# Sheet1.net
KiCad netlist of a schematic drawn in Altium Designer
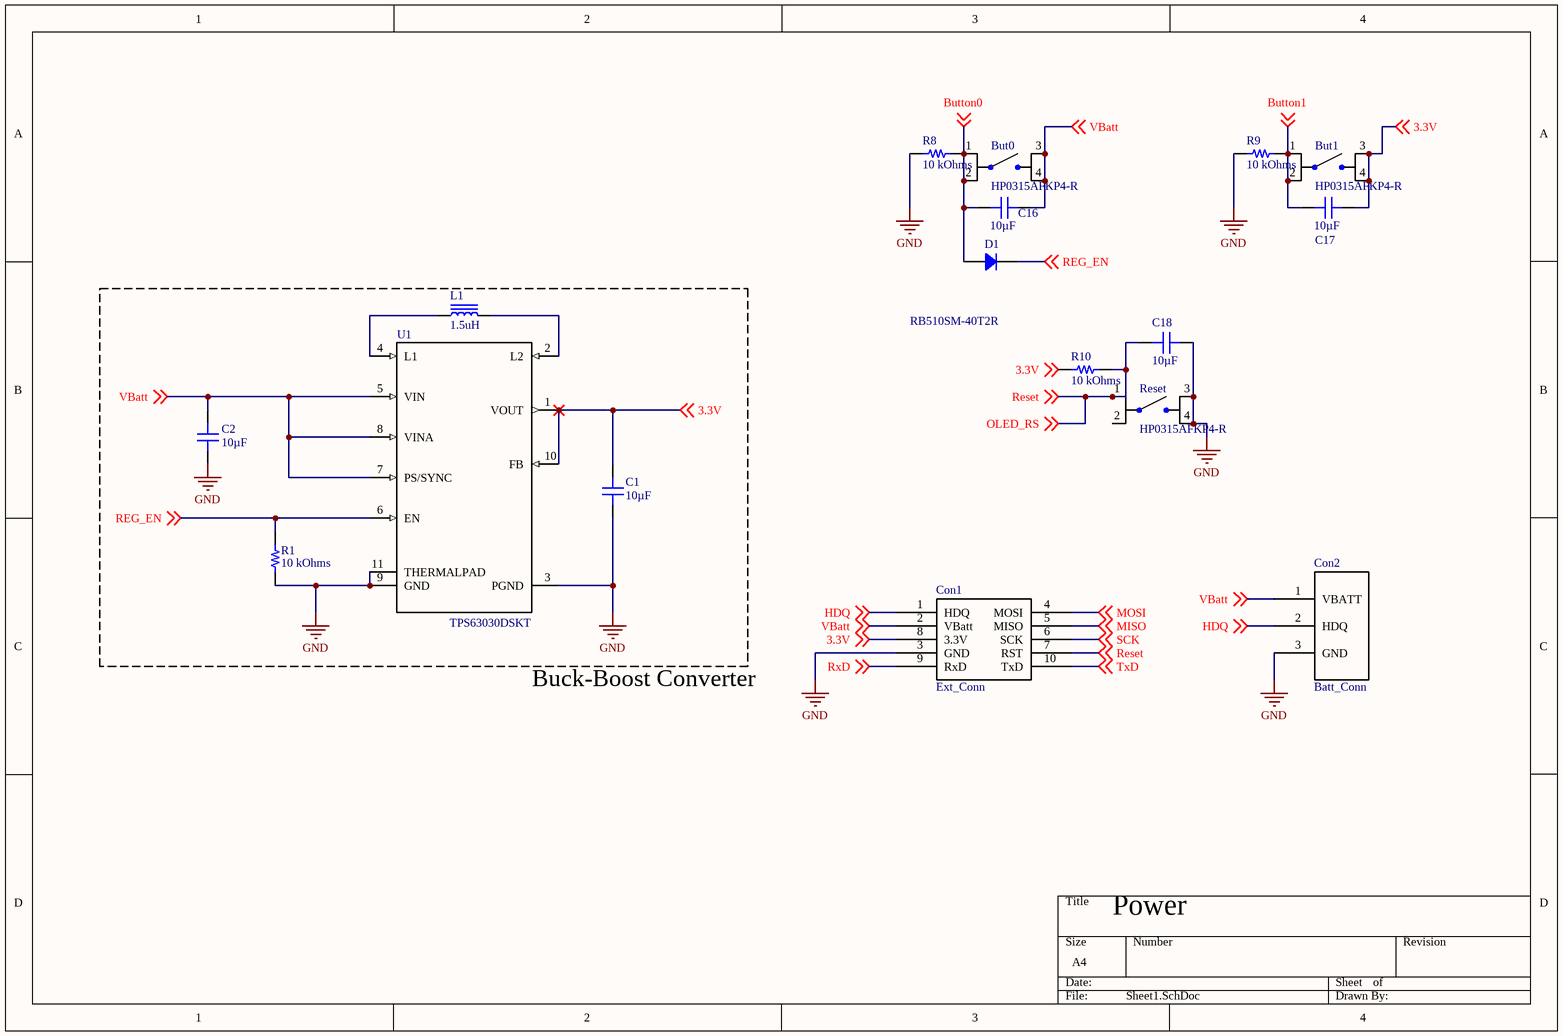
[diagram p0: Sheet1.SchDoc]

(export (version "E")
  (design (tool "Eeschema 10.0.6"))
  (components
    (comp (ref "But0")
      (value "HP0315AFKP4-R")
      (footprint "*SW_HP0315AFKP4-R")
      (description "Tactile Switch SPST-NO Top Actuated Surface Mount")
      (fields (field (name "MF") "NKK Switches"))
      (libsource (lib "ugurkrcl Lib") (part "HP0315AFKP4-R"))
    )
    (comp (ref "But1")
      (value "HP0315AFKP4-R")
      (footprint "*SW_HP0315AFKP4-R")
      (description "Tactile Switch SPST-NO Top Actuated Surface Mount")
      (fields (field (name "MF") "NKK Switches"))
      (libsource (lib "ugurkrcl Lib") (part "HP0315AFKP4-R"))
    )
    (comp (ref "C1")
      (value "10µF")
      (footprint "CAP 0402_1005")
      (description "CAP CER 10UF 10V X5R 0402")
      (fields
        (field (name "PART NUMBER") "CL05A106MP8NUB8")
        (field (name "MANUFACTURER") "Samsung Electro-Mechanics")
      )
      (libsource (lib "Celestial Altium Library - altium_library") (part "Capacitor"))
    )
    (comp (ref "C2")
      (value "10µF")
      (footprint "CAP 0402_1005")
      (description "CAP CER 10UF 10V X5R 0402")
      (fields
        (field (name "PART NUMBER") "CL05A106MP8NUB8")
        (field (name "MANUFACTURER") "Samsung Electro-Mechanics")
      )
      (libsource (lib "Celestial Altium Library - altium_library") (part "Capacitor"))
    )
    (comp (ref "C16")
      (value "10µF")
      (footprint "CAP 0402_1005")
      (description "CAP CER 10UF 10V X5R 0402")
      (fields
        (field (name "PART NUMBER") "CL05A106MP8NUB8")
        (field (name "MANUFACTURER") "Samsung Electro-Mechanics")
      )
      (libsource (lib "Celestial Altium Library - altium_library") (part "Capacitor"))
    )
    (comp (ref "C17")
      (value "10µF")
      (footprint "CAP 0402_1005")
      (description "CAP CER 10UF 10V X5R 0402")
      (fields
        (field (name "PART NUMBER") "CL05A106MP8NUB8")
        (field (name "MANUFACTURER") "Samsung Electro-Mechanics")
      )
      (libsource (lib "Celestial Altium Library - altium_library") (part "Capacitor"))
    )
    (comp (ref "C18")
      (value "10µF")
      (footprint "CAP 0402_1005")
      (description "CAP CER 10UF 10V X5R 0402")
      (fields
        (field (name "PART NUMBER") "CL05A106MP8NUB8")
        (field (name "MANUFACTURER") "Samsung Electro-Mechanics")
      )
      (libsource (lib "Celestial Altium Library - altium_library") (part "Capacitor"))
    )
    (comp (ref "Con1")
      (value "Ext_Conn")
      (footprint "JtagConn")
      (libsource (lib "BattCon") (part "Ext_Conn"))
    )
    (comp (ref "Con2")
      (value "Batt_Conn")
      (footprint "BattConn")
      (libsource (lib "ugurkrcl Lib") (part "Batt_Conn"))
    )
    (comp (ref "D1")
      (value "RB510SM-40T2R")
      (footprint "SOD-523")
      (description "RB510SM-40 IS LOW VF")
      (fields (field (name "MANUFACTURER") "Rohm Semiconductor"))
      (libsource (lib "Celestial Altium Library - altium_library") (part "Diode"))
    )
    (comp (ref "L1")
      (value "1.5uH")
      (footprint "TDK VLCF4028-2")
      (description "FIXED IND 56UH 430MA 410 MOHM")
      (fields
        (field (name "PART NUMBER") "VLCF5028T-560MR43-2")
        (field (name "MANUFACTURER") "TDK Corporation")
      )
      (libsource (lib "Celestial Altium Library - altium_library") (part "Inductor"))
    )
    (comp (ref "R1")
      (value "10 kOhms")
      (footprint "RES 0402_1005")
      (description "RES 10K OHM 0.1% 1/10W 0402")
      (fields
        (field (name "PART NUMBER") "RP73PF1E10KBTD")
        (field (name "MANUFACTURER") "TE Connectivity Passive Product")
      )
      (libsource (lib "Celestial Altium Library - altium_library") (part "Resistor"))
    )
    (comp (ref "R8")
      (value "10 kOhms")
      (footprint "RES 0402_1005")
      (description "RES 10K OHM 0.1% 1/10W 0402")
      (fields
        (field (name "PART NUMBER") "RP73PF1E10KBTD")
        (field (name "MANUFACTURER") "TE Connectivity Passive Product")
      )
      (libsource (lib "Celestial Altium Library - altium_library") (part "Resistor"))
    )
    (comp (ref "R9")
      (value "10 kOhms")
      (footprint "RES 0402_1005")
      (description "RES 10K OHM 0.1% 1/10W 0402")
      (fields
        (field (name "PART NUMBER") "RP73PF1E10KBTD")
        (field (name "MANUFACTURER") "TE Connectivity Passive Product")
      )
      (libsource (lib "Celestial Altium Library - altium_library") (part "Resistor"))
    )
    (comp (ref "R10")
      (value "10 kOhms")
      (footprint "RES 0402_1005")
      (description "RES 10K OHM 0.1% 1/10W 0402")
      (fields
        (field (name "PART NUMBER") "RP73PF1E10KBTD")
        (field (name "MANUFACTURER") "TE Connectivity Passive Product")
      )
      (libsource (lib "Celestial Altium Library - altium_library") (part "Resistor"))
    )
    (comp (ref "Reset")
      (value "HP0315AFKP4-R")
      (footprint "*SW_HP0315AFKP4-R")
      (description "Tactile Switch SPST-NO Top Actuated Surface Mount")
      (fields (field (name "MF") "NKK Switches"))
      (libsource (lib "ugurkrcl Lib") (part "HP0315AFKP4-R"))
    )
    (comp (ref "U1")
      (value "TPS63030DSKT")
      (footprint "*SON50P260X260X80-11N")
      (fields (field (name "MF") "Texas Instruments"))
      (libsource (lib "ugurkrcl Lib") (part "TPS63030DSKT"))
    )
  )
  (nets
    (net (code "1") (name "3.3V") (class "Default")
      (node (ref "But1") (pin "3") (pinfunction "3_3") (pintype "passive"))
      (node (ref "But1") (pin "4") (pinfunction "4_4") (pintype "passive"))
      (node (ref "C1") (pin "2") (pinfunction "2_2") (pintype "passive"))
      (node (ref "C17") (pin "1") (pinfunction "1_1") (pintype "passive"))
      (node (ref "Con1") (pin "8") (pinfunction "3.3V_8") (pintype "passive"))
      (node (ref "R10") (pin "2") (pinfunction "2_2") (pintype "passive"))
      (node (ref "U1") (pin "1") (pinfunction "VOUT_1") (pintype "output"))
      (node (ref "U1") (pin "10") (pinfunction "FB_10") (pintype "input"))
    )
    (net (code "2") (name "Button0") (class "Default")
      (node (ref "But0") (pin "1") (pinfunction "1_1") (pintype "passive"))
      (node (ref "But0") (pin "2") (pinfunction "2_2") (pintype "passive"))
      (node (ref "C16") (pin "2") (pinfunction "2_2") (pintype "passive"))
      (node (ref "D1") (pin "1") (pinfunction "1_1") (pintype "passive"))
      (node (ref "R8") (pin "2") (pinfunction "2_2") (pintype "passive"))
    )
    (net (code "3") (name "Button1") (class "Default")
      (node (ref "But1") (pin "1") (pinfunction "1_1") (pintype "passive"))
      (node (ref "But1") (pin "2") (pinfunction "2_2") (pintype "passive"))
      (node (ref "C17") (pin "2") (pinfunction "2_2") (pintype "passive"))
      (node (ref "R9") (pin "1") (pinfunction "1_1") (pintype "passive"))
    )
    (net (code "4") (name "GND") (class "Default")
      (node (ref "C1") (pin "1") (pinfunction "1_1") (pintype "passive"))
      (node (ref "C18") (pin "1") (pinfunction "1_1") (pintype "passive"))
      (node (ref "C2") (pin "1") (pinfunction "1_1") (pintype "passive"))
      (node (ref "Con1") (pin "3") (pinfunction "GND_3") (pintype "passive"))
      (node (ref "Con2") (pin "3") (pinfunction "GND_3") (pintype "passive"))
      (node (ref "R1") (pin "1") (pinfunction "1_1") (pintype "passive"))
      (node (ref "R8") (pin "1") (pinfunction "1_1") (pintype "passive"))
      (node (ref "R9") (pin "2") (pinfunction "2_2") (pintype "passive"))
      (node (ref "Reset") (pin "3") (pinfunction "3_3") (pintype "passive"))
      (node (ref "Reset") (pin "4") (pinfunction "4_4") (pintype "passive"))
      (node (ref "U1") (pin "11") (pinfunction "THERMALPAD_11") (pintype "passive"))
      (node (ref "U1") (pin "3") (pinfunction "PGND_3") (pintype "passive"))
      (node (ref "U1") (pin "9") (pinfunction "GND_9") (pintype "passive"))
    )
    (net (code "5") (name "HDQ") (class "Default")
      (node (ref "Con1") (pin "1") (pinfunction "HDQ_1") (pintype "passive"))
      (node (ref "Con2") (pin "2") (pinfunction "HDQ_2") (pintype "passive"))
    )
    (net (code "6") (name "MISO") (class "Default")
      (node (ref "Con1") (pin "5") (pinfunction "MISO_5") (pintype "passive"))
    )
    (net (code "7") (name "MOSI") (class "Default")
      (node (ref "Con1") (pin "4") (pinfunction "MOSI_4") (pintype "passive"))
    )
    (net (code "8") (name "Net-(U1-L1)") (class "Default")
      (node (ref "L1") (pin "1") (pinfunction "1_1") (pintype "passive"))
      (node (ref "U1") (pin "4") (pinfunction "L1_4") (pintype "input"))
    )
    (net (code "9") (name "Net-(U1-L2)") (class "Default")
      (node (ref "L1") (pin "2") (pinfunction "2_2") (pintype "passive"))
      (node (ref "U1") (pin "2") (pinfunction "L2_2") (pintype "input"))
    )
    (net (code "10") (name "OLED_RS") (class "Default")
      (node (ref "C18") (pin "2") (pinfunction "2_2") (pintype "passive"))
      (node (ref "Con1") (pin "7") (pinfunction "RST_7") (pintype "passive"))
      (node (ref "R10") (pin "1") (pinfunction "1_1") (pintype "passive"))
      (node (ref "Reset") (pin "1") (pinfunction "1_1") (pintype "passive"))
    )
    (net (code "11") (name "REG_EN") (class "Default")
      (node (ref "D1") (pin "2") (pinfunction "2_2") (pintype "passive"))
      (node (ref "R1") (pin "2") (pinfunction "2_2") (pintype "passive"))
      (node (ref "U1") (pin "6") (pinfunction "EN_6") (pintype "input"))
    )
    (net (code "12") (name "RxD") (class "Default")
      (node (ref "Con1") (pin "9") (pinfunction "RxD_9") (pintype "passive"))
    )
    (net (code "13") (name "SCK") (class "Default")
      (node (ref "Con1") (pin "6") (pinfunction "SCK_6") (pintype "passive"))
    )
    (net (code "14") (name "TxD") (class "Default")
      (node (ref "Con1") (pin "10") (pinfunction "TxD_10") (pintype "passive"))
    )
    (net (code "15") (name "VBatt") (class "Default")
      (node (ref "But0") (pin "3") (pinfunction "3_3") (pintype "passive"))
      (node (ref "But0") (pin "4") (pinfunction "4_4") (pintype "passive"))
      (node (ref "C16") (pin "1") (pinfunction "1_1") (pintype "passive"))
      (node (ref "C2") (pin "2") (pinfunction "2_2") (pintype "passive"))
      (node (ref "Con1") (pin "2") (pinfunction "VBatt_2") (pintype "passive"))
      (node (ref "Con2") (pin "1") (pinfunction "VBATT_1") (pintype "passive"))
      (node (ref "U1") (pin "5") (pinfunction "VIN_5") (pintype "input"))
      (node (ref "U1") (pin "7") (pinfunction "PS/SYNC_7") (pintype "input"))
      (node (ref "U1") (pin "8") (pinfunction "VINA_8") (pintype "input"))
    )
    (net (code "16") (name "unconnected-(Reset-Pad2)") (class "Default")
      (node (ref "Reset") (pin "2") (pinfunction "2_2") (pintype "passive"))
    )
  )
)
